# flasher.net
KiCad netlist of a schematic drawn in EAGLE
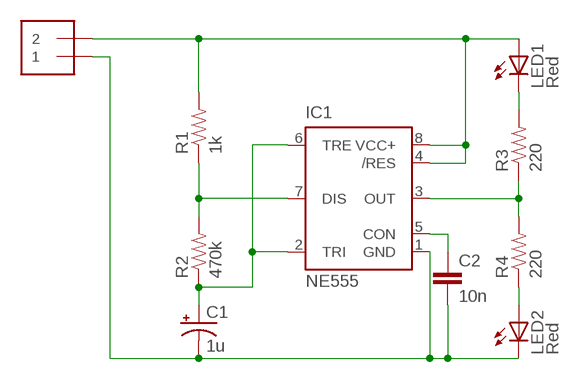
[diagram p0: schematic, sheet 1]

(export (version "E")
  (design (tool "Eeschema 10.0.6"))
  (components
    (comp (ref "C1")
      (value "1u")
      (footprint "eagle-import:CPOL-RADIAL-10UF-25V")
      (libsource (lib "eagle-import") (part "CAP_POLPTH2"))
    )
    (comp (ref "C2")
      (value "10n")
      (footprint "eagle-import:CAP-PTH-SMALL")
      (libsource (lib "eagle-import") (part "CAPPTH"))
    )
    (comp (ref "IC1")
      (value "NE555")
      (footprint "eagle-import:DIL-08")
      (fields (field (name "MF") "Arrow Electronics") (field (name "MPN") "NE555N"))
      (libsource (lib "eagle-import") (part "NE555"))
    )
    (comp (ref "J1")
      (value "1X2-3.5MM")
      (footprint "eagle-import:1X2-3.5MM")
      (libsource (lib "eagle-import") (part "1X2-3.5MM"))
    )
    (comp (ref "LED1")
      (value "Red")
      (footprint "eagle-import:LED5MM")
      (libsource (lib "eagle-import") (part "LED5MM"))
    )
    (comp (ref "LED2")
      (value "Red")
      (footprint "eagle-import:LED5MM")
      (libsource (lib "eagle-import") (part "LED5MM"))
    )
    (comp (ref "R1")
      (value "1k")
      (footprint "eagle-import:AXIAL-0.3")
      (libsource (lib "eagle-import") (part "RESISTORAXIAL-0.3"))
    )
    (comp (ref "R2")
      (value "470k")
      (footprint "eagle-import:AXIAL-0.3")
      (libsource (lib "eagle-import") (part "RESISTORAXIAL-0.3"))
    )
    (comp (ref "R3")
      (value "220")
      (footprint "eagle-import:AXIAL-0.3")
      (libsource (lib "eagle-import") (part "RESISTORAXIAL-0.3"))
    )
    (comp (ref "R4")
      (value "220")
      (footprint "eagle-import:AXIAL-0.3")
      (libsource (lib "eagle-import") (part "RESISTORAXIAL-0.3"))
    )
  )
  (nets
    (net (code "1") (name "Net-(C1-+)") (class "Default")
      (node (ref "C1") (pin "1") (pinfunction "+_1") (pintype "passive"))
      (node (ref "IC1") (pin "2") (pinfunction "TRI_2") (pintype "input"))
      (node (ref "IC1") (pin "6") (pinfunction "TRE_6") (pintype "input"))
      (node (ref "R2") (pin "P$1") (pinfunction "1_P$1") (pintype "passive"))
    )
    (net (code "2") (name "Net-(C1--)") (class "Default")
      (node (ref "C1") (pin "2") (pinfunction "-_2") (pintype "passive"))
      (node (ref "C2") (pin "2") (pinfunction "2_2") (pintype "passive"))
      (node (ref "IC1") (pin "1") (pinfunction "GND_1") (pintype "power_in"))
      (node (ref "J1") (pin "1") (pinfunction "1_1") (pintype "passive"))
      (node (ref "LED2") (pin "K") (pinfunction "C_K") (pintype "passive"))
    )
    (net (code "3") (name "Net-(IC1-CON)") (class "Default")
      (node (ref "C2") (pin "1") (pinfunction "1_1") (pintype "passive"))
      (node (ref "IC1") (pin "5") (pinfunction "CON_5") (pintype "input"))
    )
    (net (code "4") (name "Net-(IC1-DIS)") (class "Default")
      (node (ref "IC1") (pin "7") (pinfunction "DIS_7") (pintype "input"))
      (node (ref "R1") (pin "P$1") (pinfunction "1_P$1") (pintype "passive"))
      (node (ref "R2") (pin "P$2") (pinfunction "2_P$2") (pintype "passive"))
    )
    (net (code "5") (name "Net-(IC1-OUT)") (class "Default")
      (node (ref "IC1") (pin "3") (pinfunction "OUT_3") (pintype "output"))
      (node (ref "R3") (pin "P$1") (pinfunction "1_P$1") (pintype "passive"))
      (node (ref "R4") (pin "P$2") (pinfunction "2_P$2") (pintype "passive"))
    )
    (net (code "6") (name "Net-(IC1-VCC+)") (class "Default")
      (node (ref "IC1") (pin "4") (pinfunction "/RES_4") (pintype "input"))
      (node (ref "IC1") (pin "8") (pinfunction "VCC+_8") (pintype "power_in"))
      (node (ref "J1") (pin "2") (pinfunction "2_2") (pintype "passive"))
      (node (ref "LED1") (pin "A") (pinfunction "A_A") (pintype "passive"))
      (node (ref "R1") (pin "P$2") (pinfunction "2_P$2") (pintype "passive"))
    )
    (net (code "7") (name "Net-(LED1-C)") (class "Default")
      (node (ref "LED1") (pin "K") (pinfunction "C_K") (pintype "passive"))
      (node (ref "R3") (pin "P$2") (pinfunction "2_P$2") (pintype "passive"))
    )
    (net (code "8") (name "Net-(R4-1)") (class "Default")
      (node (ref "LED2") (pin "A") (pinfunction "A_A") (pintype "passive"))
      (node (ref "R4") (pin "P$1") (pinfunction "1_P$1") (pintype "passive"))
    )
  )
)
